# SCH_BitHalo_2024-01-21.net
KiCad netlist of a schematic drawn in EasyEDA
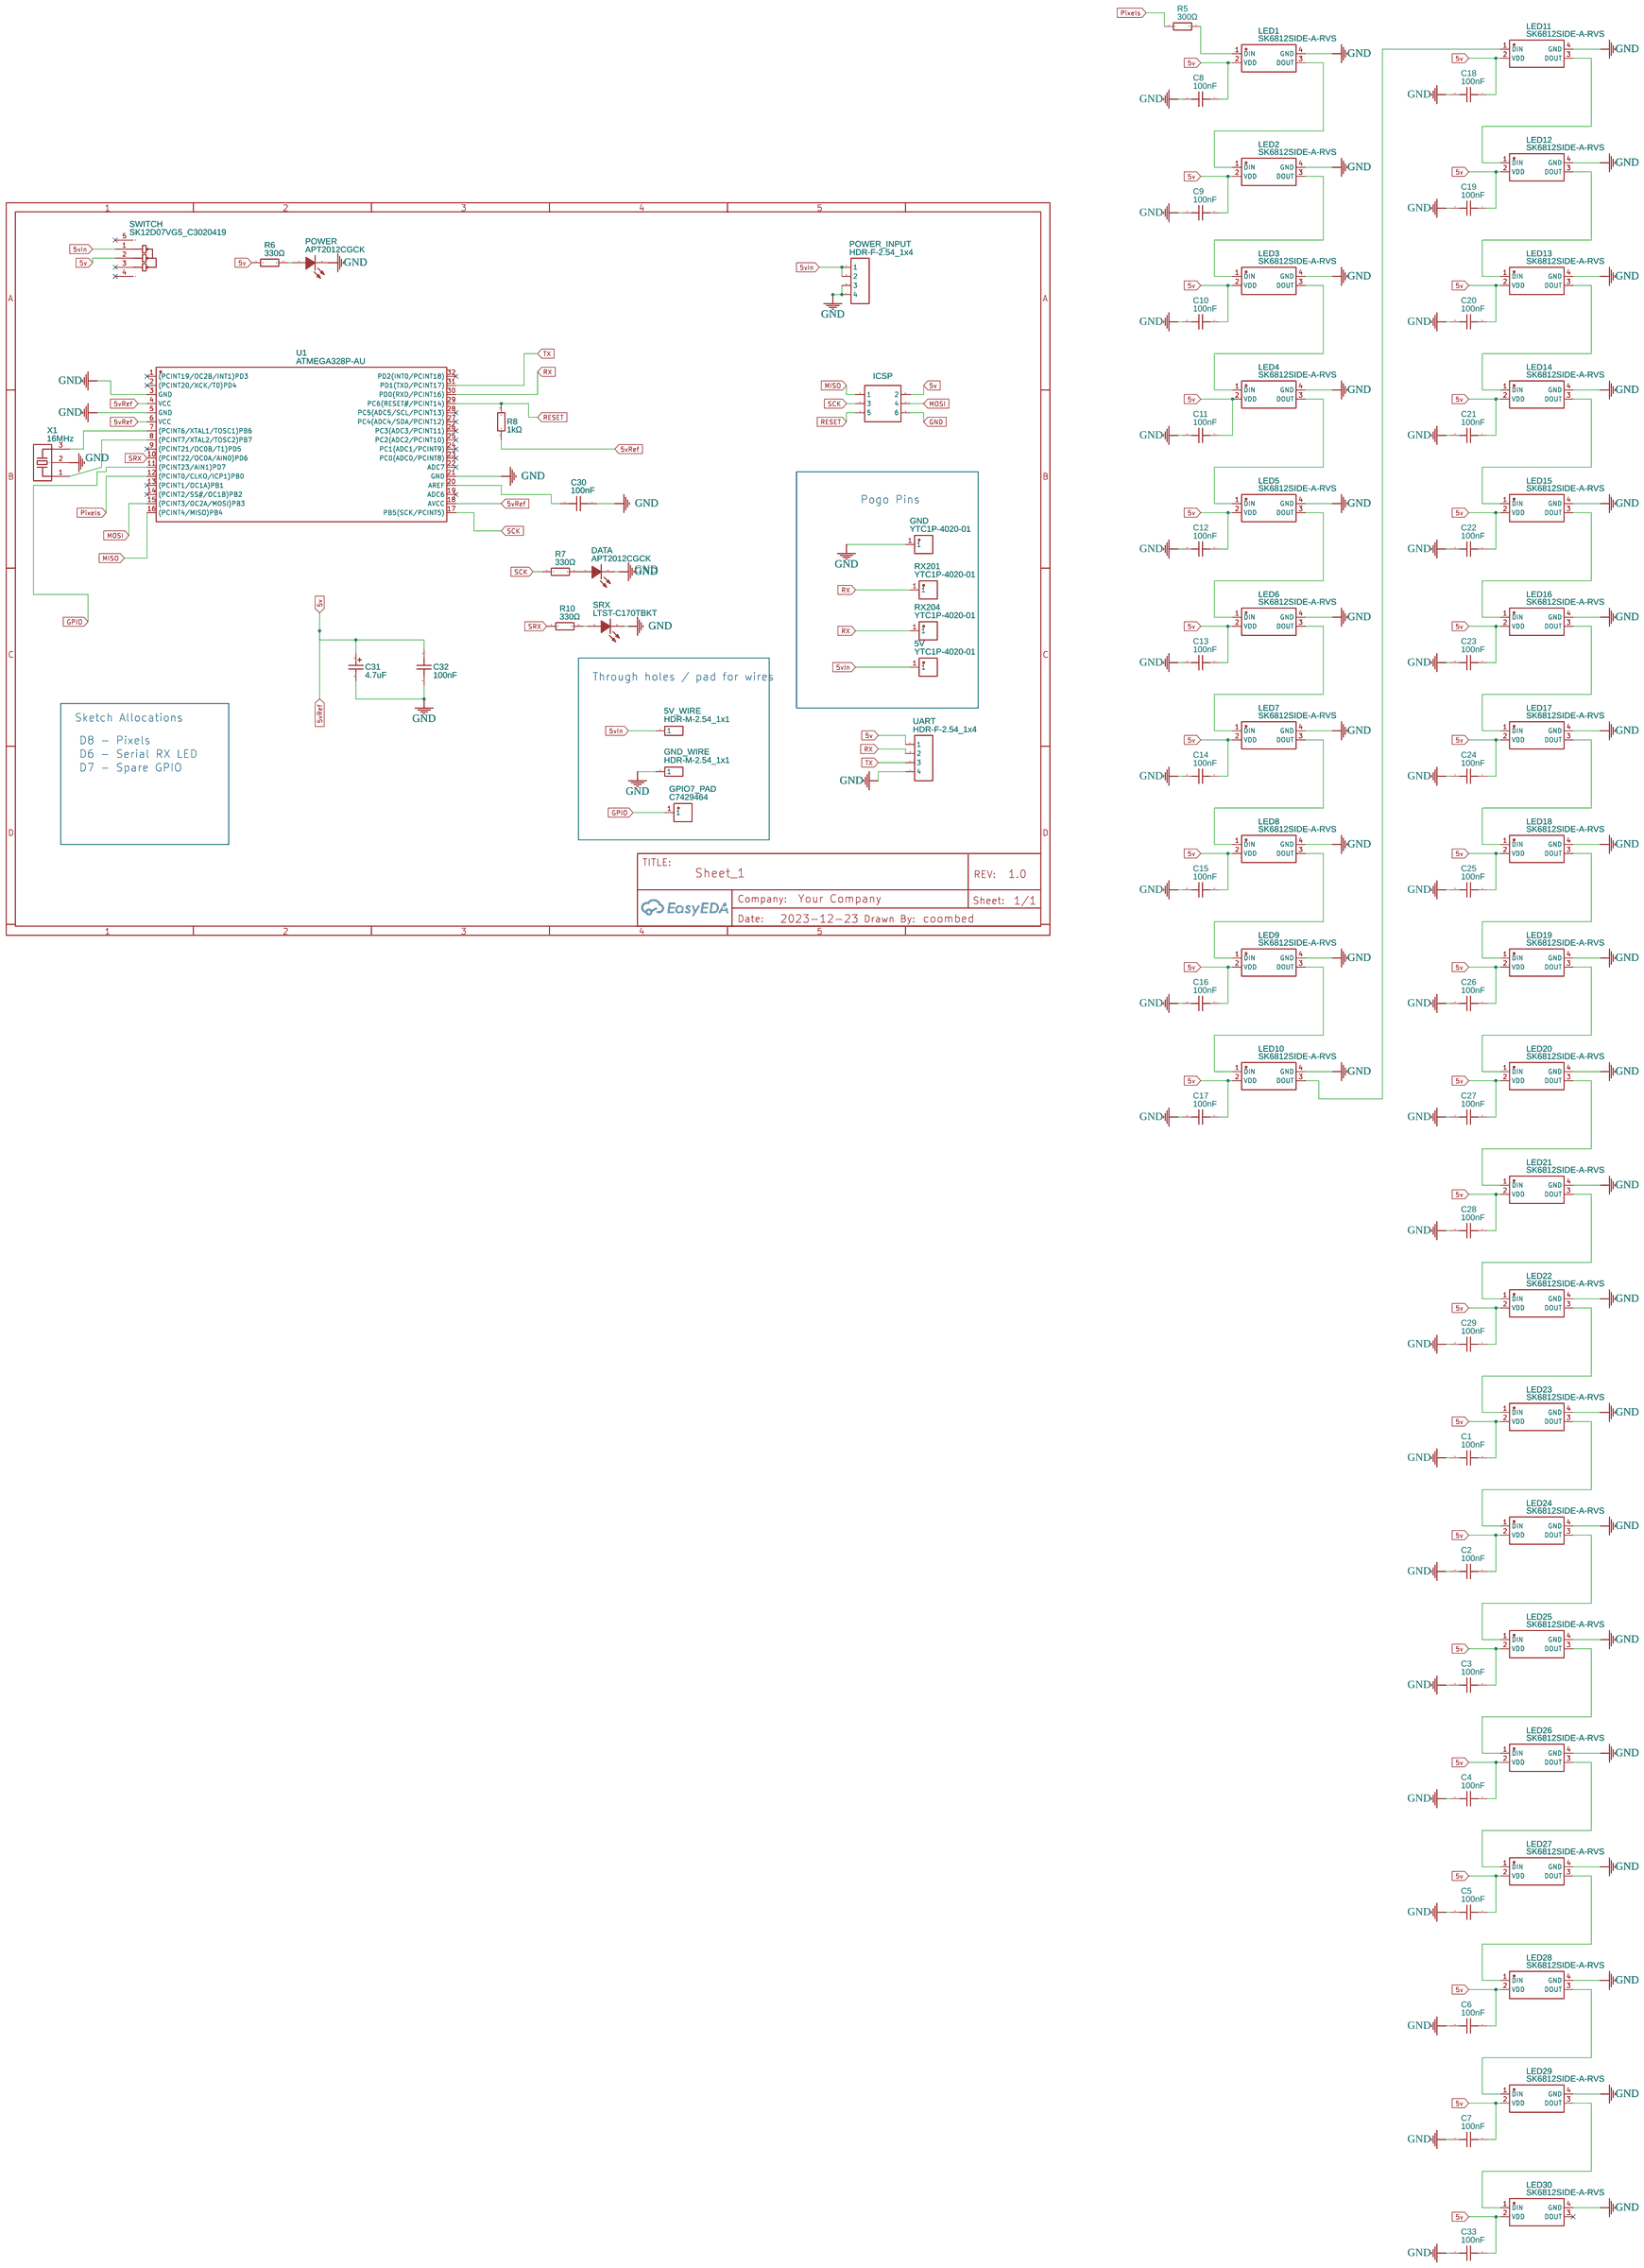
[diagram p0: schematic sheet]

(export (version "E")
  (design (tool "Eeschema 10.0.6"))
  (components
    (comp (ref "5V")
      (value "YTC1P-4020-01")
      (fields (field (name "Manufacturer") "YIYUAN(怡远)"))
      (libsource (lib "") (part "YTC1P-4020-01_2"))
    )
    (comp (ref "5V_WIRE") (value "HDR-M-2.54_1x1") (libsource (lib "") (part "HDR-M-2.54_1x1")))
    (comp (ref "C1")
      (value "100nF")
      (fields
        (field (name "Manufacturer Part") "CT41G-0402-2X1-16V-0.1μF-K(N)")
        (field (name "Manufacturer") "TORCH(火炬)")
      )
      (libsource (lib "") (part "CT41G-0402-2X1-16V-0.1μF-K(N)"))
    )
    (comp (ref "C2")
      (value "100nF")
      (fields
        (field (name "Manufacturer Part") "CT41G-0402-2X1-16V-0.1μF-K(N)")
        (field (name "Manufacturer") "TORCH(火炬)")
      )
      (libsource (lib "") (part "CT41G-0402-2X1-16V-0.1μF-K(N)"))
    )
    (comp (ref "C3")
      (value "100nF")
      (fields
        (field (name "Manufacturer Part") "CT41G-0402-2X1-16V-0.1μF-K(N)")
        (field (name "Manufacturer") "TORCH(火炬)")
      )
      (libsource (lib "") (part "CT41G-0402-2X1-16V-0.1μF-K(N)"))
    )
    (comp (ref "C4")
      (value "100nF")
      (fields
        (field (name "Manufacturer Part") "CT41G-0402-2X1-16V-0.1μF-K(N)")
        (field (name "Manufacturer") "TORCH(火炬)")
      )
      (libsource (lib "") (part "CT41G-0402-2X1-16V-0.1μF-K(N)"))
    )
    (comp (ref "C5")
      (value "100nF")
      (fields
        (field (name "Manufacturer Part") "CT41G-0402-2X1-16V-0.1μF-K(N)")
        (field (name "Manufacturer") "TORCH(火炬)")
      )
      (libsource (lib "") (part "CT41G-0402-2X1-16V-0.1μF-K(N)"))
    )
    (comp (ref "C6")
      (value "100nF")
      (fields
        (field (name "Manufacturer Part") "CT41G-0402-2X1-16V-0.1μF-K(N)")
        (field (name "Manufacturer") "TORCH(火炬)")
      )
      (libsource (lib "") (part "CT41G-0402-2X1-16V-0.1μF-K(N)"))
    )
    (comp (ref "C7")
      (value "100nF")
      (fields
        (field (name "Manufacturer Part") "CT41G-0402-2X1-16V-0.1μF-K(N)")
        (field (name "Manufacturer") "TORCH(火炬)")
      )
      (libsource (lib "") (part "CT41G-0402-2X1-16V-0.1μF-K(N)"))
    )
    (comp (ref "C8")
      (value "100nF")
      (fields
        (field (name "Manufacturer Part") "CT41G-0402-2X1-16V-0.1μF-K(N)")
        (field (name "Manufacturer") "TORCH(火炬)")
      )
      (libsource (lib "") (part "CT41G-0402-2X1-16V-0.1μF-K(N)"))
    )
    (comp (ref "C9")
      (value "100nF")
      (fields
        (field (name "Manufacturer Part") "CT41G-0402-2X1-16V-0.1μF-K(N)")
        (field (name "Manufacturer") "TORCH(火炬)")
      )
      (libsource (lib "") (part "CT41G-0402-2X1-16V-0.1μF-K(N)"))
    )
    (comp (ref "C10")
      (value "100nF")
      (fields
        (field (name "Manufacturer Part") "CT41G-0402-2X1-16V-0.1μF-K(N)")
        (field (name "Manufacturer") "TORCH(火炬)")
      )
      (libsource (lib "") (part "CT41G-0402-2X1-16V-0.1μF-K(N)"))
    )
    (comp (ref "C11")
      (value "100nF")
      (fields
        (field (name "Manufacturer Part") "CT41G-0402-2X1-16V-0.1μF-K(N)")
        (field (name "Manufacturer") "TORCH(火炬)")
      )
      (libsource (lib "") (part "CT41G-0402-2X1-16V-0.1μF-K(N)"))
    )
    (comp (ref "C12")
      (value "100nF")
      (fields
        (field (name "Manufacturer Part") "CT41G-0402-2X1-16V-0.1μF-K(N)")
        (field (name "Manufacturer") "TORCH(火炬)")
      )
      (libsource (lib "") (part "CT41G-0402-2X1-16V-0.1μF-K(N)"))
    )
    (comp (ref "C13")
      (value "100nF")
      (fields
        (field (name "Manufacturer Part") "CT41G-0402-2X1-16V-0.1μF-K(N)")
        (field (name "Manufacturer") "TORCH(火炬)")
      )
      (libsource (lib "") (part "CT41G-0402-2X1-16V-0.1μF-K(N)"))
    )
    (comp (ref "C14")
      (value "100nF")
      (fields
        (field (name "Manufacturer Part") "CT41G-0402-2X1-16V-0.1μF-K(N)")
        (field (name "Manufacturer") "TORCH(火炬)")
      )
      (libsource (lib "") (part "CT41G-0402-2X1-16V-0.1μF-K(N)"))
    )
    (comp (ref "C15")
      (value "100nF")
      (fields
        (field (name "Manufacturer Part") "CT41G-0402-2X1-16V-0.1μF-K(N)")
        (field (name "Manufacturer") "TORCH(火炬)")
      )
      (libsource (lib "") (part "CT41G-0402-2X1-16V-0.1μF-K(N)"))
    )
    (comp (ref "C16")
      (value "100nF")
      (fields
        (field (name "Manufacturer Part") "CT41G-0402-2X1-16V-0.1μF-K(N)")
        (field (name "Manufacturer") "TORCH(火炬)")
      )
      (libsource (lib "") (part "CT41G-0402-2X1-16V-0.1μF-K(N)"))
    )
    (comp (ref "C17")
      (value "100nF")
      (fields
        (field (name "Manufacturer Part") "CT41G-0402-2X1-16V-0.1μF-K(N)")
        (field (name "Manufacturer") "TORCH(火炬)")
      )
      (libsource (lib "") (part "CT41G-0402-2X1-16V-0.1μF-K(N)"))
    )
    (comp (ref "C18")
      (value "100nF")
      (fields
        (field (name "Manufacturer Part") "CT41G-0402-2X1-16V-0.1μF-K(N)")
        (field (name "Manufacturer") "TORCH(火炬)")
      )
      (libsource (lib "") (part "CT41G-0402-2X1-16V-0.1μF-K(N)"))
    )
    (comp (ref "C19")
      (value "100nF")
      (fields
        (field (name "Manufacturer Part") "CT41G-0402-2X1-16V-0.1μF-K(N)")
        (field (name "Manufacturer") "TORCH(火炬)")
      )
      (libsource (lib "") (part "CT41G-0402-2X1-16V-0.1μF-K(N)"))
    )
    (comp (ref "C20")
      (value "100nF")
      (fields
        (field (name "Manufacturer Part") "CT41G-0402-2X1-16V-0.1μF-K(N)")
        (field (name "Manufacturer") "TORCH(火炬)")
      )
      (libsource (lib "") (part "CT41G-0402-2X1-16V-0.1μF-K(N)"))
    )
    (comp (ref "C21")
      (value "100nF")
      (fields
        (field (name "Manufacturer Part") "CT41G-0402-2X1-16V-0.1μF-K(N)")
        (field (name "Manufacturer") "TORCH(火炬)")
      )
      (libsource (lib "") (part "CT41G-0402-2X1-16V-0.1μF-K(N)"))
    )
    (comp (ref "C22")
      (value "100nF")
      (fields
        (field (name "Manufacturer Part") "CT41G-0402-2X1-16V-0.1μF-K(N)")
        (field (name "Manufacturer") "TORCH(火炬)")
      )
      (libsource (lib "") (part "CT41G-0402-2X1-16V-0.1μF-K(N)"))
    )
    (comp (ref "C23")
      (value "100nF")
      (fields
        (field (name "Manufacturer Part") "CT41G-0402-2X1-16V-0.1μF-K(N)")
        (field (name "Manufacturer") "TORCH(火炬)")
      )
      (libsource (lib "") (part "CT41G-0402-2X1-16V-0.1μF-K(N)"))
    )
    (comp (ref "C24")
      (value "100nF")
      (fields
        (field (name "Manufacturer Part") "CT41G-0402-2X1-16V-0.1μF-K(N)")
        (field (name "Manufacturer") "TORCH(火炬)")
      )
      (libsource (lib "") (part "CT41G-0402-2X1-16V-0.1μF-K(N)"))
    )
    (comp (ref "C25")
      (value "100nF")
      (fields
        (field (name "Manufacturer Part") "CT41G-0402-2X1-16V-0.1μF-K(N)")
        (field (name "Manufacturer") "TORCH(火炬)")
      )
      (libsource (lib "") (part "CT41G-0402-2X1-16V-0.1μF-K(N)"))
    )
    (comp (ref "C26")
      (value "100nF")
      (fields
        (field (name "Manufacturer Part") "CT41G-0402-2X1-16V-0.1μF-K(N)")
        (field (name "Manufacturer") "TORCH(火炬)")
      )
      (libsource (lib "") (part "CT41G-0402-2X1-16V-0.1μF-K(N)"))
    )
    (comp (ref "C27")
      (value "100nF")
      (fields
        (field (name "Manufacturer Part") "CT41G-0402-2X1-16V-0.1μF-K(N)")
        (field (name "Manufacturer") "TORCH(火炬)")
      )
      (libsource (lib "") (part "CT41G-0402-2X1-16V-0.1μF-K(N)"))
    )
    (comp (ref "C28")
      (value "100nF")
      (fields
        (field (name "Manufacturer Part") "CT41G-0402-2X1-16V-0.1μF-K(N)")
        (field (name "Manufacturer") "TORCH(火炬)")
      )
      (libsource (lib "") (part "CT41G-0402-2X1-16V-0.1μF-K(N)"))
    )
    (comp (ref "C29")
      (value "100nF")
      (fields
        (field (name "Manufacturer Part") "CT41G-0402-2X1-16V-0.1μF-K(N)")
        (field (name "Manufacturer") "TORCH(火炬)")
      )
      (libsource (lib "") (part "CT41G-0402-2X1-16V-0.1μF-K(N)"))
    )
    (comp (ref "C30")
      (value "100nF")
      (fields (field (name "Manufacturer Part") "C0805C104K5RACTU") (field (name "Manufacturer") "KEMET(基美)"))
      (libsource (lib "") (part "C0805C104K5RACTU_C3018562"))
    )
    (comp (ref "C31")
      (value "4.7uF")
      (fields (field (name "Manufacturer Part") "CA45-A016K475T") (field (name "Manufacturer") "湘怡中元/湘江"))
      (libsource (lib "") (part "CA45-A016K475T"))
    )
    (comp (ref "C32")
      (value "100nF")
      (fields (field (name "Manufacturer Part") "C0805C104K5RACTU") (field (name "Manufacturer") "KEMET(基美)"))
      (libsource (lib "") (part "C0805C104K5RACTU_C3018562_1"))
    )
    (comp (ref "C33")
      (value "100nF")
      (fields
        (field (name "Manufacturer Part") "CT41G-0402-2X1-16V-0.1μF-K(N)")
        (field (name "Manufacturer") "TORCH(火炬)")
      )
      (libsource (lib "") (part "CT41G-0402-2X1-16V-0.1μF-K(N)"))
    )
    (comp (ref "DATA")
      (value "APT2012CGCK")
      (fields (field (name "Manufacturer") "Kingbright"))
      (libsource (lib "") (part "APT2012CGCK_1"))
    )
    (comp (ref "GND")
      (value "YTC1P-4020-01")
      (fields (field (name "Manufacturer") "YIYUAN(怡远)"))
      (libsource (lib "") (part "YTC1P-4020-01_1"))
    )
    (comp (ref "GND_WIRE") (value "HDR-M-2.54_1x1") (libsource (lib "") (part "HDR-M-2.54_1x1_1")))
    (comp (ref "GPIO7_PAD")
      (value "C7429464")
      (fields (field (name "Manufacturer Part") "YTC1P-2510-01") (field (name "Manufacturer") "YIYUAN(怡远)"))
      (libsource (lib "") (part "YTC1P-2510-01"))
    )
    (comp (ref "ICSP")
      (value "Header-Male-2.54_2x3")
      (fields (field (name "Manufacturer Part") "2.54-2*3P针") (field (name "Manufacturer") "BOOMELE(博穆精密)"))
      (libsource (lib "") (part "Header-Male-2.54_2x3"))
    )
    (comp (ref "LED1")
      (value "SK6812SIDE-A-RVS")
      (fields (field (name "Manufacturer") "欧思科光电"))
      (libsource (lib "") (part "SK6812SIDE-A-RVS"))
    )
    (comp (ref "LED2")
      (value "SK6812SIDE-A-RVS")
      (fields (field (name "Manufacturer") "欧思科光电"))
      (libsource (lib "") (part "SK6812SIDE-A-RVS"))
    )
    (comp (ref "LED3")
      (value "SK6812SIDE-A-RVS")
      (fields (field (name "Manufacturer") "欧思科光电"))
      (libsource (lib "") (part "SK6812SIDE-A-RVS"))
    )
    (comp (ref "LED4")
      (value "SK6812SIDE-A-RVS")
      (fields (field (name "Manufacturer") "欧思科光电"))
      (libsource (lib "") (part "SK6812SIDE-A-RVS"))
    )
    (comp (ref "LED5")
      (value "SK6812SIDE-A-RVS")
      (fields (field (name "Manufacturer") "欧思科光电"))
      (libsource (lib "") (part "SK6812SIDE-A-RVS"))
    )
    (comp (ref "LED6")
      (value "SK6812SIDE-A-RVS")
      (fields (field (name "Manufacturer") "欧思科光电"))
      (libsource (lib "") (part "SK6812SIDE-A-RVS"))
    )
    (comp (ref "LED7")
      (value "SK6812SIDE-A-RVS")
      (fields (field (name "Manufacturer") "欧思科光电"))
      (libsource (lib "") (part "SK6812SIDE-A-RVS"))
    )
    (comp (ref "LED8")
      (value "SK6812SIDE-A-RVS")
      (fields (field (name "Manufacturer") "欧思科光电"))
      (libsource (lib "") (part "SK6812SIDE-A-RVS"))
    )
    (comp (ref "LED9")
      (value "SK6812SIDE-A-RVS")
      (fields (field (name "Manufacturer") "欧思科光电"))
      (libsource (lib "") (part "SK6812SIDE-A-RVS"))
    )
    (comp (ref "LED10")
      (value "SK6812SIDE-A-RVS")
      (fields (field (name "Manufacturer") "欧思科光电"))
      (libsource (lib "") (part "SK6812SIDE-A-RVS"))
    )
    (comp (ref "LED11")
      (value "SK6812SIDE-A-RVS")
      (fields (field (name "Manufacturer") "欧思科光电"))
      (libsource (lib "") (part "SK6812SIDE-A-RVS"))
    )
    (comp (ref "LED12")
      (value "SK6812SIDE-A-RVS")
      (fields (field (name "Manufacturer") "欧思科光电"))
      (libsource (lib "") (part "SK6812SIDE-A-RVS"))
    )
    (comp (ref "LED13")
      (value "SK6812SIDE-A-RVS")
      (fields (field (name "Manufacturer") "欧思科光电"))
      (libsource (lib "") (part "SK6812SIDE-A-RVS"))
    )
    (comp (ref "LED14")
      (value "SK6812SIDE-A-RVS")
      (fields (field (name "Manufacturer") "欧思科光电"))
      (libsource (lib "") (part "SK6812SIDE-A-RVS"))
    )
    (comp (ref "LED15")
      (value "SK6812SIDE-A-RVS")
      (fields (field (name "Manufacturer") "欧思科光电"))
      (libsource (lib "") (part "SK6812SIDE-A-RVS"))
    )
    (comp (ref "LED16")
      (value "SK6812SIDE-A-RVS")
      (fields (field (name "Manufacturer") "欧思科光电"))
      (libsource (lib "") (part "SK6812SIDE-A-RVS"))
    )
    (comp (ref "LED17")
      (value "SK6812SIDE-A-RVS")
      (fields (field (name "Manufacturer") "欧思科光电"))
      (libsource (lib "") (part "SK6812SIDE-A-RVS"))
    )
    (comp (ref "LED18")
      (value "SK6812SIDE-A-RVS")
      (fields (field (name "Manufacturer") "欧思科光电"))
      (libsource (lib "") (part "SK6812SIDE-A-RVS"))
    )
    (comp (ref "LED19")
      (value "SK6812SIDE-A-RVS")
      (fields (field (name "Manufacturer") "欧思科光电"))
      (libsource (lib "") (part "SK6812SIDE-A-RVS"))
    )
    (comp (ref "LED20")
      (value "SK6812SIDE-A-RVS")
      (fields (field (name "Manufacturer") "欧思科光电"))
      (libsource (lib "") (part "SK6812SIDE-A-RVS"))
    )
    (comp (ref "LED21")
      (value "SK6812SIDE-A-RVS")
      (fields (field (name "Manufacturer") "欧思科光电"))
      (libsource (lib "") (part "SK6812SIDE-A-RVS"))
    )
    (comp (ref "LED22")
      (value "SK6812SIDE-A-RVS")
      (fields (field (name "Manufacturer") "欧思科光电"))
      (libsource (lib "") (part "SK6812SIDE-A-RVS"))
    )
    (comp (ref "LED23")
      (value "SK6812SIDE-A-RVS")
      (fields (field (name "Manufacturer") "欧思科光电"))
      (libsource (lib "") (part "SK6812SIDE-A-RVS"))
    )
    (comp (ref "LED24")
      (value "SK6812SIDE-A-RVS")
      (fields (field (name "Manufacturer") "欧思科光电"))
      (libsource (lib "") (part "SK6812SIDE-A-RVS"))
    )
    (comp (ref "LED25")
      (value "SK6812SIDE-A-RVS")
      (fields (field (name "Manufacturer") "欧思科光电"))
      (libsource (lib "") (part "SK6812SIDE-A-RVS"))
    )
    (comp (ref "LED26")
      (value "SK6812SIDE-A-RVS")
      (fields (field (name "Manufacturer") "欧思科光电"))
      (libsource (lib "") (part "SK6812SIDE-A-RVS"))
    )
    (comp (ref "LED27")
      (value "SK6812SIDE-A-RVS")
      (fields (field (name "Manufacturer") "欧思科光电"))
      (libsource (lib "") (part "SK6812SIDE-A-RVS"))
    )
    (comp (ref "LED28")
      (value "SK6812SIDE-A-RVS")
      (fields (field (name "Manufacturer") "欧思科光电"))
      (libsource (lib "") (part "SK6812SIDE-A-RVS"))
    )
    (comp (ref "LED29")
      (value "SK6812SIDE-A-RVS")
      (fields (field (name "Manufacturer") "欧思科光电"))
      (libsource (lib "") (part "SK6812SIDE-A-RVS"))
    )
    (comp (ref "LED30")
      (value "SK6812SIDE-A-RVS")
      (fields (field (name "Manufacturer") "欧思科光电"))
      (libsource (lib "") (part "SK6812SIDE-A-RVS"))
    )
    (comp (ref "POWER")
      (value "APT2012CGCK")
      (fields (field (name "Manufacturer") "Kingbright"))
      (libsource (lib "") (part "APT2012CGCK"))
    )
    (comp (ref "POWER_INPUT") (value "HDR-F-2.54_1x4") (libsource (lib "") (part "HDR-F-2.54_1x4_1")))
    (comp (ref "R5")
      (value "300Ω")
      (fields
        (field (name "Manufacturer Part") "0603WAF3000T5E")
        (field (name "Manufacturer") "UNI-ROYAL(厚声)")
      )
      (libsource (lib "") (part "0603WAF3000T5E"))
    )
    (comp (ref "R6")
      (value "330Ω")
      (fields
        (field (name "Manufacturer Part") "0402WGF6800TCE")
        (field (name "Manufacturer") "UNI-ROYAL(厚声)")
      )
      (libsource (lib "") (part "0402WGF6800TCE"))
    )
    (comp (ref "R7")
      (value "330Ω")
      (fields
        (field (name "Manufacturer Part") "0402WGF6800TCE")
        (field (name "Manufacturer") "UNI-ROYAL(厚声)")
      )
      (libsource (lib "") (part "0402WGF6800TCE"))
    )
    (comp (ref "R8")
      (value "1kΩ")
      (fields (field (name "Manufacturer Part") "RC0402FR-071KL") (field (name "Manufacturer") "YAGEO(国巨)"))
      (libsource (lib "") (part "RC0402FR-071KL"))
    )
    (comp (ref "R10")
      (value "330Ω")
      (fields
        (field (name "Manufacturer Part") "0402WGF6800TCE")
        (field (name "Manufacturer") "UNI-ROYAL(厚声)")
      )
      (libsource (lib "") (part "0402WGF6800TCE"))
    )
    (comp (ref "RX201")
      (value "YTC1P-4020-01")
      (fields (field (name "Manufacturer") "YIYUAN(怡远)"))
      (libsource (lib "") (part "YTC1P-4020-01"))
    )
    (comp (ref "RX204")
      (value "YTC1P-4020-01")
      (fields (field (name "Manufacturer") "YIYUAN(怡远)"))
      (libsource (lib "") (part "YTC1P-4020-01"))
    )
    (comp (ref "SRX")
      (value "LTST-C170TBKT")
      (fields (field (name "Manufacturer") "LITEON(光宝)"))
      (libsource (lib "") (part "LTST-C170TBKT"))
    )
    (comp (ref "SWITCH")
      (value "SK12D07VG5_C3020419")
      (fields (field (name "Manufacturer Part") "SK12D07VG5") (field (name "Manufacturer") "SHOU HAN(首韩)"))
      (libsource (lib "") (part "SK12D07VG5_C3020419"))
    )
    (comp (ref "U1")
      (value "ATMEGA328P-AU")
      (fields (field (name "Manufacturer") "MICROCHIP(美国微芯)"))
      (libsource (lib "") (part "ATMEGA328P-AU"))
    )
    (comp (ref "UART") (value "HDR-F-2.54_1x4") (libsource (lib "") (part "HDR-F-2.54_1x4")))
    (comp (ref "X1")
      (value "16MHz")
      (fields (field (name "Manufacturer Part") "CSTCE16M0V53-R0") (field (name "Manufacturer") "muRata(村田)"))
      (libsource (lib "") (part "CSTCE16M0V53-R0"))
    )
  )
  (nets
    (net (code "1") (name "5v") (class "Default")
      (node (ref "C1") (pin "1") (pinfunction "1_1") (pintype "unspecified"))
      (node (ref "C10") (pin "1") (pinfunction "1_1") (pintype "unspecified"))
      (node (ref "C11") (pin "1") (pinfunction "1_1") (pintype "unspecified"))
      (node (ref "C12") (pin "1") (pinfunction "1_1") (pintype "unspecified"))
      (node (ref "C13") (pin "1") (pinfunction "1_1") (pintype "unspecified"))
      (node (ref "C14") (pin "1") (pinfunction "1_1") (pintype "unspecified"))
      (node (ref "C15") (pin "1") (pinfunction "1_1") (pintype "unspecified"))
      (node (ref "C16") (pin "1") (pinfunction "1_1") (pintype "unspecified"))
      (node (ref "C17") (pin "1") (pinfunction "1_1") (pintype "unspecified"))
      (node (ref "C18") (pin "1") (pinfunction "1_1") (pintype "unspecified"))
      (node (ref "C19") (pin "1") (pinfunction "1_1") (pintype "unspecified"))
      (node (ref "C2") (pin "1") (pinfunction "1_1") (pintype "unspecified"))
      (node (ref "C20") (pin "1") (pinfunction "1_1") (pintype "unspecified"))
      (node (ref "C21") (pin "1") (pinfunction "1_1") (pintype "unspecified"))
      (node (ref "C22") (pin "1") (pinfunction "1_1") (pintype "unspecified"))
      (node (ref "C23") (pin "1") (pinfunction "1_1") (pintype "unspecified"))
      (node (ref "C24") (pin "1") (pinfunction "1_1") (pintype "unspecified"))
      (node (ref "C25") (pin "1") (pinfunction "1_1") (pintype "unspecified"))
      (node (ref "C26") (pin "1") (pinfunction "1_1") (pintype "unspecified"))
      (node (ref "C27") (pin "1") (pinfunction "1_1") (pintype "unspecified"))
      (node (ref "C28") (pin "1") (pinfunction "1_1") (pintype "unspecified"))
      (node (ref "C29") (pin "1") (pinfunction "1_1") (pintype "unspecified"))
      (node (ref "C3") (pin "1") (pinfunction "1_1") (pintype "unspecified"))
      (node (ref "C31") (pin "1") (pinfunction "1_1") (pintype "input"))
      (node (ref "C32") (pin "1") (pinfunction "1_1") (pintype "unspecified"))
      (node (ref "C33") (pin "1") (pinfunction "1_1") (pintype "unspecified"))
      (node (ref "C4") (pin "1") (pinfunction "1_1") (pintype "unspecified"))
      (node (ref "C5") (pin "1") (pinfunction "1_1") (pintype "unspecified"))
      (node (ref "C6") (pin "1") (pinfunction "1_1") (pintype "unspecified"))
      (node (ref "C7") (pin "1") (pinfunction "1_1") (pintype "unspecified"))
      (node (ref "C8") (pin "1") (pinfunction "1_1") (pintype "unspecified"))
      (node (ref "C9") (pin "1") (pinfunction "1_1") (pintype "unspecified"))
      (node (ref "ICSP") (pin "2") (pinfunction "2_2") (pintype "input"))
      (node (ref "LED1") (pin "2") (pinfunction "VDD_2") (pintype "unspecified"))
      (node (ref "LED10") (pin "2") (pinfunction "VDD_2") (pintype "unspecified"))
      (node (ref "LED11") (pin "2") (pinfunction "VDD_2") (pintype "unspecified"))
      (node (ref "LED12") (pin "2") (pinfunction "VDD_2") (pintype "unspecified"))
      (node (ref "LED13") (pin "2") (pinfunction "VDD_2") (pintype "unspecified"))
      (node (ref "LED14") (pin "2") (pinfunction "VDD_2") (pintype "unspecified"))
      (node (ref "LED15") (pin "2") (pinfunction "VDD_2") (pintype "unspecified"))
      (node (ref "LED16") (pin "2") (pinfunction "VDD_2") (pintype "unspecified"))
      (node (ref "LED17") (pin "2") (pinfunction "VDD_2") (pintype "unspecified"))
      (node (ref "LED18") (pin "2") (pinfunction "VDD_2") (pintype "unspecified"))
      (node (ref "LED19") (pin "2") (pinfunction "VDD_2") (pintype "unspecified"))
      (node (ref "LED2") (pin "2") (pinfunction "VDD_2") (pintype "unspecified"))
      (node (ref "LED20") (pin "2") (pinfunction "VDD_2") (pintype "unspecified"))
      (node (ref "LED21") (pin "2") (pinfunction "VDD_2") (pintype "unspecified"))
      (node (ref "LED22") (pin "2") (pinfunction "VDD_2") (pintype "unspecified"))
      (node (ref "LED23") (pin "2") (pinfunction "VDD_2") (pintype "unspecified"))
      (node (ref "LED24") (pin "2") (pinfunction "VDD_2") (pintype "unspecified"))
      (node (ref "LED25") (pin "2") (pinfunction "VDD_2") (pintype "unspecified"))
      (node (ref "LED26") (pin "2") (pinfunction "VDD_2") (pintype "unspecified"))
      (node (ref "LED27") (pin "2") (pinfunction "VDD_2") (pintype "unspecified"))
      (node (ref "LED28") (pin "2") (pinfunction "VDD_2") (pintype "unspecified"))
      (node (ref "LED29") (pin "2") (pinfunction "VDD_2") (pintype "unspecified"))
      (node (ref "LED3") (pin "2") (pinfunction "VDD_2") (pintype "unspecified"))
      (node (ref "LED30") (pin "2") (pinfunction "VDD_2") (pintype "unspecified"))
      (node (ref "LED4") (pin "2") (pinfunction "VDD_2") (pintype "unspecified"))
      (node (ref "LED5") (pin "2") (pinfunction "VDD_2") (pintype "unspecified"))
      (node (ref "LED6") (pin "2") (pinfunction "VDD_2") (pintype "unspecified"))
      (node (ref "LED7") (pin "2") (pinfunction "VDD_2") (pintype "unspecified"))
      (node (ref "LED8") (pin "2") (pinfunction "VDD_2") (pintype "unspecified"))
      (node (ref "LED9") (pin "2") (pinfunction "VDD_2") (pintype "unspecified"))
      (node (ref "R6") (pin "1") (pinfunction "1_1") (pintype "input"))
      (node (ref "R8") (pin "1") (pinfunction "1_1") (pintype "input"))
      (node (ref "SWITCH") (pin "2") (pinfunction "2_2") (pintype "unspecified"))
      (node (ref "U1") (pin "18") (pinfunction "AVCC_18") (pintype "unspecified"))
      (node (ref "U1") (pin "4") (pinfunction "VCC_4") (pintype "unspecified"))
      (node (ref "U1") (pin "6") (pinfunction "VCC_6") (pintype "unspecified"))
      (node (ref "UART") (pin "1") (pinfunction "1_1") (pintype "unspecified"))
    )
    (net (code "2") (name "5vIn") (class "Default")
      (node (ref "5V") (pin "1") (pinfunction "1_1") (pintype "unspecified"))
      (node (ref "5V_WIRE") (pin "1") (pinfunction "1_1") (pintype "input"))
      (node (ref "POWER_INPUT") (pin "1") (pinfunction "1_1") (pintype "unspecified"))
      (node (ref "POWER_INPUT") (pin "2") (pinfunction "2_2") (pintype "unspecified"))
      (node (ref "SWITCH") (pin "1") (pinfunction "1_1") (pintype "unspecified"))
    )
    (net (code "3") (name "GND") (class "Default")
      (node (ref "C1") (pin "2") (pinfunction "2_2") (pintype "unspecified"))
      (node (ref "C10") (pin "2") (pinfunction "2_2") (pintype "unspecified"))
      (node (ref "C11") (pin "2") (pinfunction "2_2") (pintype "unspecified"))
      (node (ref "C12") (pin "2") (pinfunction "2_2") (pintype "unspecified"))
      (node (ref "C13") (pin "2") (pinfunction "2_2") (pintype "unspecified"))
      (node (ref "C14") (pin "2") (pinfunction "2_2") (pintype "unspecified"))
      (node (ref "C15") (pin "2") (pinfunction "2_2") (pintype "unspecified"))
      (node (ref "C16") (pin "2") (pinfunction "2_2") (pintype "unspecified"))
      (node (ref "C17") (pin "2") (pinfunction "2_2") (pintype "unspecified"))
      (node (ref "C18") (pin "2") (pinfunction "2_2") (pintype "unspecified"))
      (node (ref "C19") (pin "2") (pinfunction "2_2") (pintype "unspecified"))
      (node (ref "C2") (pin "2") (pinfunction "2_2") (pintype "unspecified"))
      (node (ref "C20") (pin "2") (pinfunction "2_2") (pintype "unspecified"))
      (node (ref "C21") (pin "2") (pinfunction "2_2") (pintype "unspecified"))
      (node (ref "C22") (pin "2") (pinfunction "2_2") (pintype "unspecified"))
      (node (ref "C23") (pin "2") (pinfunction "2_2") (pintype "unspecified"))
      (node (ref "C24") (pin "2") (pinfunction "2_2") (pintype "unspecified"))
      (node (ref "C25") (pin "2") (pinfunction "2_2") (pintype "unspecified"))
      (node (ref "C26") (pin "2") (pinfunction "2_2") (pintype "unspecified"))
      (node (ref "C27") (pin "2") (pinfunction "2_2") (pintype "unspecified"))
      (node (ref "C28") (pin "2") (pinfunction "2_2") (pintype "unspecified"))
      (node (ref "C29") (pin "2") (pinfunction "2_2") (pintype "unspecified"))
      (node (ref "C3") (pin "2") (pinfunction "2_2") (pintype "unspecified"))
      (node (ref "C30") (pin "2") (pinfunction "2_2") (pintype "unspecified"))
      (node (ref "C31") (pin "2") (pinfunction "2_2") (pintype "input"))
      (node (ref "C32") (pin "2") (pinfunction "2_2") (pintype "unspecified"))
      (node (ref "C33") (pin "2") (pinfunction "2_2") (pintype "unspecified"))
      (node (ref "C4") (pin "2") (pinfunction "2_2") (pintype "unspecified"))
      (node (ref "C5") (pin "2") (pinfunction "2_2") (pintype "unspecified"))
      (node (ref "C6") (pin "2") (pinfunction "2_2") (pintype "unspecified"))
      (node (ref "C7") (pin "2") (pinfunction "2_2") (pintype "unspecified"))
      (node (ref "C8") (pin "2") (pinfunction "2_2") (pintype "unspecified"))
      (node (ref "C9") (pin "2") (pinfunction "2_2") (pintype "unspecified"))
      (node (ref "DATA") (pin "2") (pinfunction "K_2") (pintype "unspecified"))
      (node (ref "GND") (pin "1") (pinfunction "1_1") (pintype "unspecified"))
      (node (ref "GND_WIRE") (pin "1") (pinfunction "1_1") (pintype "input"))
      (node (ref "ICSP") (pin "6") (pinfunction "6_6") (pintype "input"))
      (node (ref "LED1") (pin "4") (pinfunction "GND_4") (pintype "unspecified"))
      (node (ref "LED10") (pin "4") (pinfunction "GND_4") (pintype "unspecified"))
      (node (ref "LED11") (pin "4") (pinfunction "GND_4") (pintype "unspecified"))
      (node (ref "LED12") (pin "4") (pinfunction "GND_4") (pintype "unspecified"))
      (node (ref "LED13") (pin "4") (pinfunction "GND_4") (pintype "unspecified"))
      (node (ref "LED14") (pin "4") (pinfunction "GND_4") (pintype "unspecified"))
      (node (ref "LED15") (pin "4") (pinfunction "GND_4") (pintype "unspecified"))
      (node (ref "LED16") (pin "4") (pinfunction "GND_4") (pintype "unspecified"))
      (node (ref "LED17") (pin "4") (pinfunction "GND_4") (pintype "unspecified"))
      (node (ref "LED18") (pin "4") (pinfunction "GND_4") (pintype "unspecified"))
      (node (ref "LED19") (pin "4") (pinfunction "GND_4") (pintype "unspecified"))
      (node (ref "LED2") (pin "4") (pinfunction "GND_4") (pintype "unspecified"))
      (node (ref "LED20") (pin "4") (pinfunction "GND_4") (pintype "unspecified"))
      (node (ref "LED21") (pin "4") (pinfunction "GND_4") (pintype "unspecified"))
      (node (ref "LED22") (pin "4") (pinfunction "GND_4") (pintype "unspecified"))
      (node (ref "LED23") (pin "4") (pinfunction "GND_4") (pintype "unspecified"))
      (node (ref "LED24") (pin "4") (pinfunction "GND_4") (pintype "unspecified"))
      (node (ref "LED25") (pin "4") (pinfunction "GND_4") (pintype "unspecified"))
      (node (ref "LED26") (pin "4") (pinfunction "GND_4") (pintype "unspecified"))
      (node (ref "LED27") (pin "4") (pinfunction "GND_4") (pintype "unspecified"))
      (node (ref "LED28") (pin "4") (pinfunction "GND_4") (pintype "unspecified"))
      (node (ref "LED29") (pin "4") (pinfunction "GND_4") (pintype "unspecified"))
      (node (ref "LED3") (pin "4") (pinfunction "GND_4") (pintype "unspecified"))
      (node (ref "LED30") (pin "4") (pinfunction "GND_4") (pintype "unspecified"))
      (node (ref "LED4") (pin "4") (pinfunction "GND_4") (pintype "unspecified"))
      (node (ref "LED5") (pin "4") (pinfunction "GND_4") (pintype "unspecified"))
      (node (ref "LED6") (pin "4") (pinfunction "GND_4") (pintype "unspecified"))
      (node (ref "LED7") (pin "4") (pinfunction "GND_4") (pintype "unspecified"))
      (node (ref "LED8") (pin "4") (pinfunction "GND_4") (pintype "unspecified"))
      (node (ref "LED9") (pin "4") (pinfunction "GND_4") (pintype "unspecified"))
      (node (ref "POWER") (pin "2") (pinfunction "K_2") (pintype "unspecified"))
      (node (ref "POWER_INPUT") (pin "3") (pinfunction "3_3") (pintype "unspecified"))
      (node (ref "POWER_INPUT") (pin "4") (pinfunction "4_4") (pintype "unspecified"))
      (node (ref "SRX") (pin "1") (pinfunction "K_1") (pintype "unspecified"))
      (node (ref "U1") (pin "21") (pinfunction "GND_21") (pintype "unspecified"))
      (node (ref "U1") (pin "3") (pinfunction "GND_3") (pintype "unspecified"))
      (node (ref "U1") (pin "5") (pinfunction "GND_5") (pintype "unspecified"))
      (node (ref "UART") (pin "4") (pinfunction "4_4") (pintype "unspecified"))
      (node (ref "X1") (pin "2") (pinfunction "2_2") (pintype "unspecified"))
    )
    (net (code "4") (name "GPIO") (class "Default")
      (node (ref "GPIO7_PAD") (pin "1") (pinfunction "1_1") (pintype "unspecified"))
      (node (ref "U1") (pin "11") (pinfunction "(PCINT23/AIN1)PD7_11") (pintype "unspecified"))
    )
    (net (code "5") (name "MISO") (class "Default")
      (node (ref "ICSP") (pin "1") (pinfunction "1_1") (pintype "input"))
      (node (ref "U1") (pin "16") (pinfunction "(PCINT4/MISO)PB4_16") (pintype "unspecified"))
    )
    (net (code "6") (name "MOSI") (class "Default")
      (node (ref "ICSP") (pin "4") (pinfunction "4_4") (pintype "input"))
      (node (ref "U1") (pin "15") (pinfunction "(PCINT3/OC2A/MOSI)PB3_15") (pintype "unspecified"))
    )
    (net (code "7") (name "Net-(DATA-A)") (class "Default")
      (node (ref "DATA") (pin "1") (pinfunction "A_1") (pintype "unspecified"))
      (node (ref "R7") (pin "2") (pinfunction "2_2") (pintype "input"))
    )
    (net (code "8") (name "Net-(LED1-DIN)") (class "Default")
      (node (ref "LED1") (pin "1") (pinfunction "DIN_1") (pintype "unspecified"))
      (node (ref "R5") (pin "2") (pinfunction "2_2") (pintype "input"))
    )
    (net (code "9") (name "Net-(LED1-DOUT)") (class "Default")
      (node (ref "LED1") (pin "3") (pinfunction "DOUT_3") (pintype "unspecified"))
      (node (ref "LED2") (pin "1") (pinfunction "DIN_1") (pintype "unspecified"))
    )
    (net (code "10") (name "Net-(LED2-DOUT)") (class "Default")
      (node (ref "LED2") (pin "3") (pinfunction "DOUT_3") (pintype "unspecified"))
      (node (ref "LED3") (pin "1") (pinfunction "DIN_1") (pintype "unspecified"))
    )
    (net (code "11") (name "Net-(LED3-DOUT)") (class "Default")
      (node (ref "LED3") (pin "3") (pinfunction "DOUT_3") (pintype "unspecified"))
      (node (ref "LED4") (pin "1") (pinfunction "DIN_1") (pintype "unspecified"))
    )
    (net (code "12") (name "Net-(LED4-DOUT)") (class "Default")
      (node (ref "LED4") (pin "3") (pinfunction "DOUT_3") (pintype "unspecified"))
      (node (ref "LED5") (pin "1") (pinfunction "DIN_1") (pintype "unspecified"))
    )
    (net (code "13") (name "Net-(LED5-DOUT)") (class "Default")
      (node (ref "LED5") (pin "3") (pinfunction "DOUT_3") (pintype "unspecified"))
      (node (ref "LED6") (pin "1") (pinfunction "DIN_1") (pintype "unspecified"))
    )
    (net (code "14") (name "Net-(LED6-DOUT)") (class "Default")
      (node (ref "LED6") (pin "3") (pinfunction "DOUT_3") (pintype "unspecified"))
      (node (ref "LED7") (pin "1") (pinfunction "DIN_1") (pintype "unspecified"))
    )
    (net (code "15") (name "Net-(LED7-DOUT)") (class "Default")
      (node (ref "LED7") (pin "3") (pinfunction "DOUT_3") (pintype "unspecified"))
      (node (ref "LED8") (pin "1") (pinfunction "DIN_1") (pintype "unspecified"))
    )
    (net (code "16") (name "Net-(LED8-DOUT)") (class "Default")
      (node (ref "LED8") (pin "3") (pinfunction "DOUT_3") (pintype "unspecified"))
      (node (ref "LED9") (pin "1") (pinfunction "DIN_1") (pintype "unspecified"))
    )
    (net (code "17") (name "Net-(LED10-DIN)") (class "Default")
      (node (ref "LED10") (pin "1") (pinfunction "DIN_1") (pintype "unspecified"))
      (node (ref "LED9") (pin "3") (pinfunction "DOUT_3") (pintype "unspecified"))
    )
    (net (code "18") (name "Net-(LED10-DOUT)") (class "Default")
      (node (ref "LED10") (pin "3") (pinfunction "DOUT_3") (pintype "unspecified"))
      (node (ref "LED11") (pin "1") (pinfunction "DIN_1") (pintype "unspecified"))
    )
    (net (code "19") (name "Net-(LED11-DOUT)") (class "Default")
      (node (ref "LED11") (pin "3") (pinfunction "DOUT_3") (pintype "unspecified"))
      (node (ref "LED12") (pin "1") (pinfunction "DIN_1") (pintype "unspecified"))
    )
    (net (code "20") (name "Net-(LED12-DOUT)") (class "Default")
      (node (ref "LED12") (pin "3") (pinfunction "DOUT_3") (pintype "unspecified"))
      (node (ref "LED13") (pin "1") (pinfunction "DIN_1") (pintype "unspecified"))
    )
    (net (code "21") (name "Net-(LED13-DOUT)") (class "Default")
      (node (ref "LED13") (pin "3") (pinfunction "DOUT_3") (pintype "unspecified"))
      (node (ref "LED14") (pin "1") (pinfunction "DIN_1") (pintype "unspecified"))
    )
    (net (code "22") (name "Net-(LED14-DOUT)") (class "Default")
      (node (ref "LED14") (pin "3") (pinfunction "DOUT_3") (pintype "unspecified"))
      (node (ref "LED15") (pin "1") (pinfunction "DIN_1") (pintype "unspecified"))
    )
    (net (code "23") (name "Net-(LED15-DOUT)") (class "Default")
      (node (ref "LED15") (pin "3") (pinfunction "DOUT_3") (pintype "unspecified"))
      (node (ref "LED16") (pin "1") (pinfunction "DIN_1") (pintype "unspecified"))
    )
    (net (code "24") (name "Net-(LED16-DOUT)") (class "Default")
      (node (ref "LED16") (pin "3") (pinfunction "DOUT_3") (pintype "unspecified"))
      (node (ref "LED17") (pin "1") (pinfunction "DIN_1") (pintype "unspecified"))
    )
    (net (code "25") (name "Net-(LED17-DOUT)") (class "Default")
      (node (ref "LED17") (pin "3") (pinfunction "DOUT_3") (pintype "unspecified"))
      (node (ref "LED18") (pin "1") (pinfunction "DIN_1") (pintype "unspecified"))
    )
    (net (code "26") (name "Net-(LED18-DOUT)") (class "Default")
      (node (ref "LED18") (pin "3") (pinfunction "DOUT_3") (pintype "unspecified"))
      (node (ref "LED19") (pin "1") (pinfunction "DIN_1") (pintype "unspecified"))
    )
    (net (code "27") (name "Net-(LED19-DOUT)") (class "Default")
      (node (ref "LED19") (pin "3") (pinfunction "DOUT_3") (pintype "unspecified"))
      (node (ref "LED20") (pin "1") (pinfunction "DIN_1") (pintype "unspecified"))
    )
    (net (code "28") (name "Net-(LED20-DOUT)") (class "Default")
      (node (ref "LED20") (pin "3") (pinfunction "DOUT_3") (pintype "unspecified"))
      (node (ref "LED21") (pin "1") (pinfunction "DIN_1") (pintype "unspecified"))
    )
    (net (code "29") (name "Net-(LED21-DOUT)") (class "Default")
      (node (ref "LED21") (pin "3") (pinfunction "DOUT_3") (pintype "unspecified"))
      (node (ref "LED22") (pin "1") (pinfunction "DIN_1") (pintype "unspecified"))
    )
    (net (code "30") (name "Net-(LED22-DOUT)") (class "Default")
      (node (ref "LED22") (pin "3") (pinfunction "DOUT_3") (pintype "unspecified"))
      (node (ref "LED23") (pin "1") (pinfunction "DIN_1") (pintype "unspecified"))
    )
    (net (code "31") (name "Net-(LED23-DOUT)") (class "Default")
      (node (ref "LED23") (pin "3") (pinfunction "DOUT_3") (pintype "unspecified"))
      (node (ref "LED24") (pin "1") (pinfunction "DIN_1") (pintype "unspecified"))
    )
    (net (code "32") (name "Net-(LED24-DOUT)") (class "Default")
      (node (ref "LED24") (pin "3") (pinfunction "DOUT_3") (pintype "unspecified"))
      (node (ref "LED25") (pin "1") (pinfunction "DIN_1") (pintype "unspecified"))
    )
    (net (code "33") (name "Net-(LED25-DOUT)") (class "Default")
      (node (ref "LED25") (pin "3") (pinfunction "DOUT_3") (pintype "unspecified"))
      (node (ref "LED26") (pin "1") (pinfunction "DIN_1") (pintype "unspecified"))
    )
    (net (code "34") (name "Net-(LED26-DOUT)") (class "Default")
      (node (ref "LED26") (pin "3") (pinfunction "DOUT_3") (pintype "unspecified"))
      (node (ref "LED27") (pin "1") (pinfunction "DIN_1") (pintype "unspecified"))
    )
    (net (code "35") (name "Net-(LED27-DOUT)") (class "Default")
      (node (ref "LED27") (pin "3") (pinfunction "DOUT_3") (pintype "unspecified"))
      (node (ref "LED28") (pin "1") (pinfunction "DIN_1") (pintype "unspecified"))
    )
    (net (code "36") (name "Net-(LED28-DOUT)") (class "Default")
      (node (ref "LED28") (pin "3") (pinfunction "DOUT_3") (pintype "unspecified"))
      (node (ref "LED29") (pin "1") (pinfunction "DIN_1") (pintype "unspecified"))
    )
    (net (code "37") (name "Net-(LED29-DOUT)") (class "Default")
      (node (ref "LED29") (pin "3") (pinfunction "DOUT_3") (pintype "unspecified"))
      (node (ref "LED30") (pin "1") (pinfunction "DIN_1") (pintype "unspecified"))
    )
    (net (code "38") (name "Net-(POWER-A)") (class "Default")
      (node (ref "POWER") (pin "1") (pinfunction "A_1") (pintype "unspecified"))
      (node (ref "R6") (pin "2") (pinfunction "2_2") (pintype "input"))
    )
    (net (code "39") (name "Net-(SRX-A)") (class "Default")
      (node (ref "R10") (pin "2") (pinfunction "2_2") (pintype "input"))
      (node (ref "SRX") (pin "2") (pinfunction "A_2") (pintype "unspecified"))
    )
    (net (code "40") (name "Net-(U1-(PCINT6{slash}XTAL1{slash}TOSC1)PB6)") (class "Default")
      (node (ref "U1") (pin "7") (pinfunction "(PCINT6/XTAL1/TOSC1)PB6_7") (pintype "unspecified"))
      (node (ref "X1") (pin "3") (pinfunction "3_3") (pintype "unspecified"))
    )
    (net (code "41") (name "Net-(U1-(PCINT7{slash}XTAL2{slash}TOSC2)PB7)") (class "Default")
      (node (ref "U1") (pin "8") (pinfunction "(PCINT7/XTAL2/TOSC2)PB7_8") (pintype "unspecified"))
      (node (ref "X1") (pin "1") (pinfunction "1_1") (pintype "unspecified"))
    )
    (net (code "42") (name "Net-(U1-AREF)") (class "Default")
      (node (ref "C30") (pin "1") (pinfunction "1_1") (pintype "unspecified"))
      (node (ref "U1") (pin "20") (pinfunction "AREF_20") (pintype "unspecified"))
    )
    (net (code "43") (name "Pixels") (class "Default")
      (node (ref "R5") (pin "1") (pinfunction "1_1") (pintype "input"))
      (node (ref "U1") (pin "12") (pinfunction "(PCINT0/CLKO/ICP1)PB0_12") (pintype "unspecified"))
    )
    (net (code "44") (name "RESET") (class "Default")
      (node (ref "ICSP") (pin "5") (pinfunction "5_5") (pintype "input"))
      (node (ref "R8") (pin "2") (pinfunction "2_2") (pintype "input"))
      (node (ref "U1") (pin "29") (pinfunction "PC6(RESET#/PCINT14)_29") (pintype "unspecified"))
    )
    (net (code "45") (name "RX") (class "Default")
      (node (ref "RX201") (pin "1") (pinfunction "1_1") (pintype "unspecified"))
      (node (ref "RX204") (pin "1") (pinfunction "1_1") (pintype "unspecified"))
      (node (ref "U1") (pin "30") (pinfunction "PD0(RXD/PCINT16)_30") (pintype "unspecified"))
      (node (ref "UART") (pin "2") (pinfunction "2_2") (pintype "unspecified"))
    )
    (net (code "46") (name "SCK") (class "Default")
      (node (ref "ICSP") (pin "3") (pinfunction "3_3") (pintype "input"))
      (node (ref "R7") (pin "1") (pinfunction "1_1") (pintype "input"))
      (node (ref "U1") (pin "17") (pinfunction "PB5(SCK/PCINT5)_17") (pintype "unspecified"))
    )
    (net (code "47") (name "SRX") (class "Default")
      (node (ref "R10") (pin "1") (pinfunction "1_1") (pintype "input"))
      (node (ref "U1") (pin "10") (pinfunction "(PCINT22/OC0A/AIN0)PD6_10") (pintype "unspecified"))
    )
    (net (code "48") (name "TX") (class "Default")
      (node (ref "U1") (pin "31") (pinfunction "PD1(TXD/PCINT17)_31") (pintype "unspecified"))
      (node (ref "UART") (pin "3") (pinfunction "3_3") (pintype "unspecified"))
    )
    (net (code "49") (name "unconnected-(LED30-DOUT-Pad3)") (class "Default")
      (node (ref "LED30") (pin "3") (pinfunction "DOUT_3") (pintype "unspecified+no_connect"))
    )
    (net (code "50") (name "unconnected-(SWITCH-Pad3)") (class "Default")
      (node (ref "SWITCH") (pin "3") (pinfunction "3_3") (pintype "unspecified+no_connect"))
    )
    (net (code "51") (name "unconnected-(SWITCH-Pad4)") (class "Default")
      (node (ref "SWITCH") (pin "4") (pinfunction "4_4") (pintype "unspecified+no_connect"))
    )
    (net (code "52") (name "unconnected-(SWITCH-Pad5)") (class "Default")
      (node (ref "SWITCH") (pin "5") (pinfunction "5_5") (pintype "unspecified+no_connect"))
    )
    (net (code "53") (name "unconnected-(U1-(PCINT1{slash}OC1A)PB1-Pad13)") (class "Default")
      (node (ref "U1") (pin "13") (pinfunction "(PCINT1/OC1A)PB1_13") (pintype "unspecified+no_connect"))
    )
    (net (code "54") (name "unconnected-(U1-(PCINT2{slash}SS#{slash}OC1B)PB2-Pad14)") (class "Default")
      (node (ref "U1") (pin "14") (pinfunction "(PCINT2/SS#/OC1B)PB2_14") (pintype "unspecified+no_connect"))
    )
    (net (code "55") (name "unconnected-(U1-(PCINT19{slash}OC2B{slash}INT1)PD3-Pad1)") (class "Default")
      (node (ref "U1") (pin "1") (pinfunction "(PCINT19/OC2B/INT1)PD3_1") (pintype "unspecified+no_connect"))
    )
    (net (code "56") (name "unconnected-(U1-(PCINT20{slash}XCK{slash}T0)PD4-Pad2)") (class "Default")
      (node (ref "U1") (pin "2") (pinfunction "(PCINT20/XCK/T0)PD4_2") (pintype "unspecified+no_connect"))
    )
    (net (code "57") (name "unconnected-(U1-(PCINT21{slash}OC0B{slash}T1)PD5-Pad9)") (class "Default")
      (node (ref "U1") (pin "9") (pinfunction "(PCINT21/OC0B/T1)PD5_9") (pintype "unspecified+no_connect"))
    )
    (net (code "58") (name "unconnected-(U1-ADC6-Pad19)") (class "Default")
      (node (ref "U1") (pin "19") (pinfunction "ADC6_19") (pintype "unspecified+no_connect"))
    )
    (net (code "59") (name "unconnected-(U1-ADC7-Pad22)") (class "Default")
      (node (ref "U1") (pin "22") (pinfunction "ADC7_22") (pintype "unspecified+no_connect"))
    )
    (net (code "60") (name "unconnected-(U1-PC0(ADC0{slash}PCINT8)-Pad23)") (class "Default")
      (node (ref "U1") (pin "23") (pinfunction "PC0(ADC0/PCINT8)_23") (pintype "unspecified+no_connect"))
    )
    (net (code "61") (name "unconnected-(U1-PC1(ADC1{slash}PCINT9)-Pad24)") (class "Default")
      (node (ref "U1") (pin "24") (pinfunction "PC1(ADC1/PCINT9)_24") (pintype "unspecified+no_connect"))
    )
    (net (code "62") (name "unconnected-(U1-PC2(ADC2{slash}PCINT10)-Pad25)") (class "Default")
      (node (ref "U1") (pin "25") (pinfunction "PC2(ADC2/PCINT10)_25") (pintype "unspecified+no_connect"))
    )
    (net (code "63") (name "unconnected-(U1-PC3(ADC3{slash}PCINT11)-Pad26)") (class "Default")
      (node (ref "U1") (pin "26") (pinfunction "PC3(ADC3/PCINT11)_26") (pintype "unspecified+no_connect"))
    )
    (net (code "64") (name "unconnected-(U1-PC4(ADC4{slash}SDA{slash}PCINT12)-Pad27)") (class "Default")
      (node (ref "U1") (pin "27") (pinfunction "PC4(ADC4/SDA/PCINT12)_27") (pintype "unspecified+no_connect"))
    )
    (net (code "65") (name "unconnected-(U1-PC5(ADC5{slash}SCL{slash}PCINT13)-Pad28)") (class "Default")
      (node (ref "U1") (pin "28") (pinfunction "PC5(ADC5/SCL/PCINT13)_28") (pintype "unspecified+no_connect"))
    )
    (net (code "66") (name "unconnected-(U1-PD2(INT0{slash}PCINT18)-Pad32)") (class "Default")
      (node (ref "U1") (pin "32") (pinfunction "PD2(INT0/PCINT18)_32") (pintype "unspecified+no_connect"))
    )
  )
)
